# PentaFnord_CtrlBoard_0_91.net
KiCad netlist of a schematic drawn in EAGLE
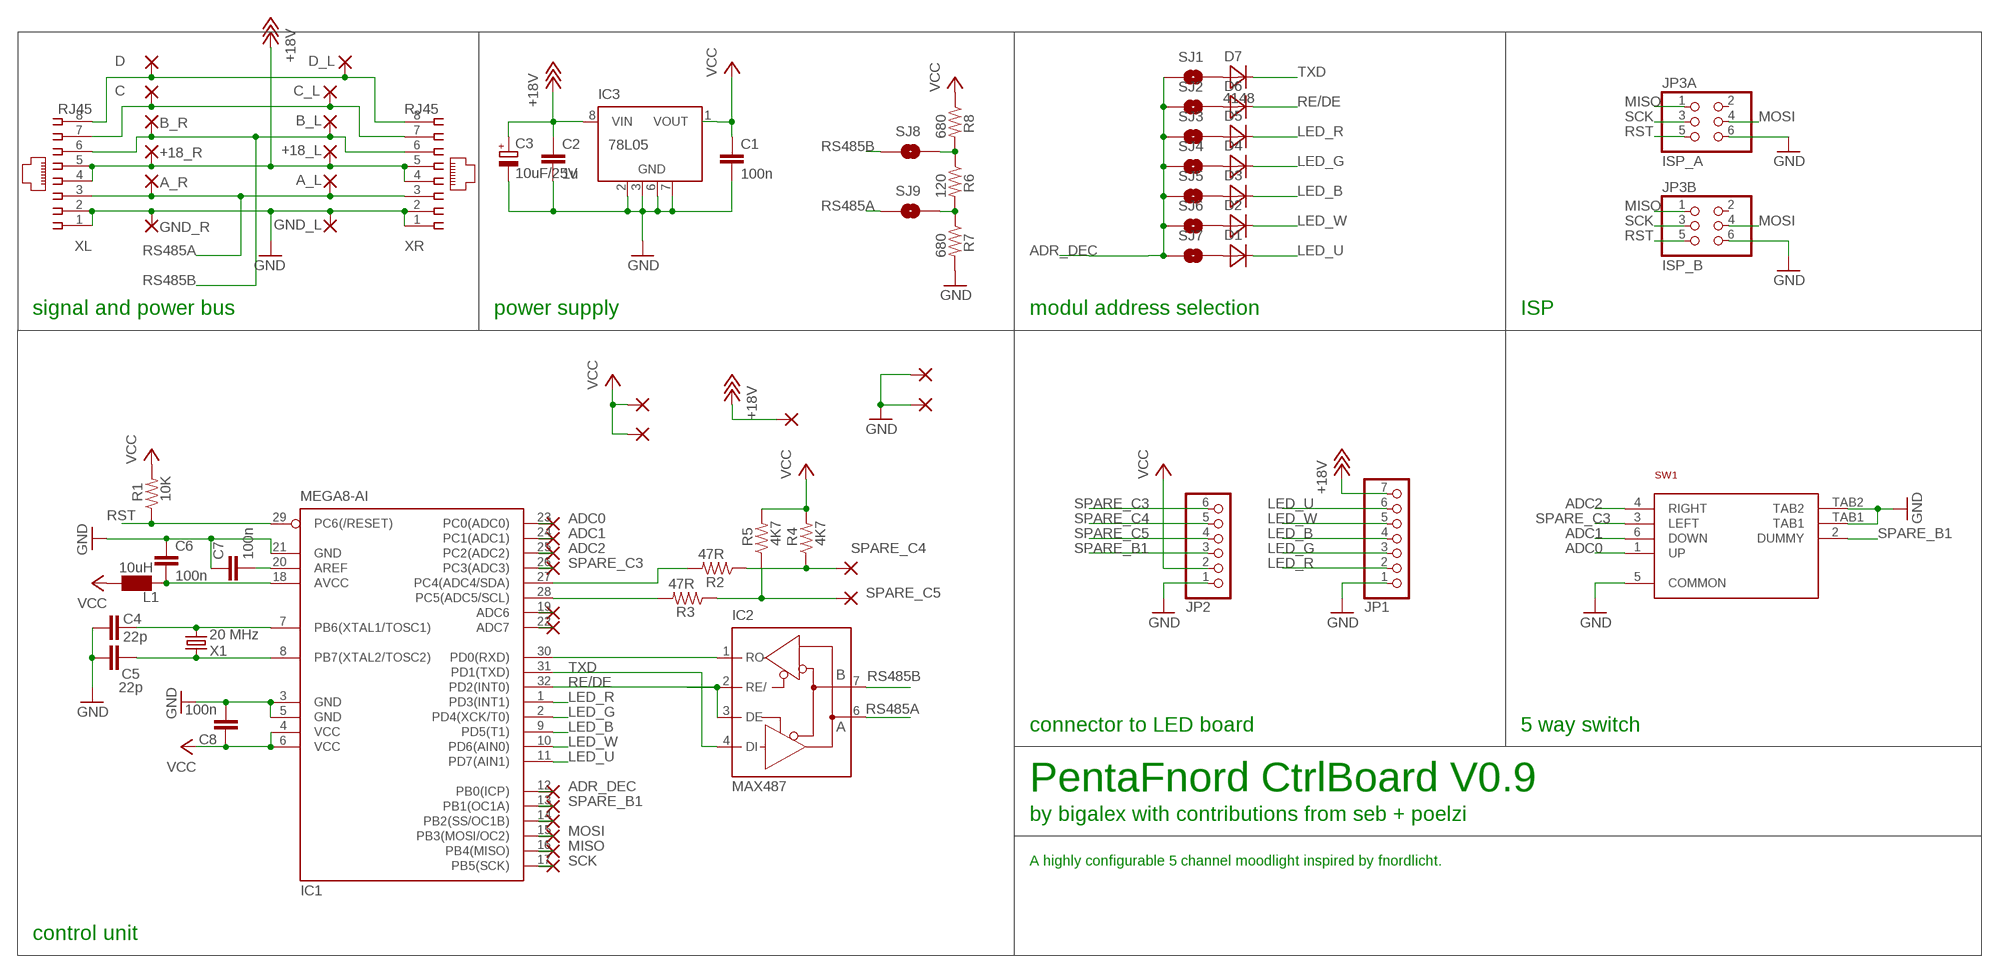
[diagram p0: schematic, sheet 1]

(export (version "E")
  (design (tool "Eeschema 10.0.6"))
  (components
    (comp (ref "+18_L")
      (value "WIREPADSMD2,54-5,08")
      (footprint "eagle-import:SMD2,54-5,08")
      (libsource (lib "eagle-import") (part "WIREPADSMD2,54-5,08"))
    )
    (comp (ref "+18_R")
      (value "WIREPADSMD2,54-5,08")
      (footprint "eagle-import:SMD2,54-5,08")
      (libsource (lib "eagle-import") (part "WIREPADSMD2,54-5,08"))
    )
    (comp (ref "ADC6")
      (value "WIREPADSMD1,27-254")
      (footprint "eagle-import:SMD1,27-2,54")
      (libsource (lib "eagle-import") (part "WIREPADSMD1,27-254"))
    )
    (comp (ref "ADC7")
      (value "WIREPADSMD1,27-254")
      (footprint "eagle-import:SMD1,27-2,54")
      (libsource (lib "eagle-import") (part "WIREPADSMD1,27-254"))
    )
    (comp (ref "A_L")
      (value "WIREPADSMD1,27-254")
      (footprint "eagle-import:SMD1,27-2,54")
      (libsource (lib "eagle-import") (part "WIREPADSMD1,27-254"))
    )
    (comp (ref "A_R")
      (value "WIREPADSMD1,27-254")
      (footprint "eagle-import:SMD1,27-2,54")
      (libsource (lib "eagle-import") (part "WIREPADSMD1,27-254"))
    )
    (comp (ref "B_L")
      (value "WIREPADSMD1,27-254")
      (footprint "eagle-import:SMD1,27-2,54")
      (libsource (lib "eagle-import") (part "WIREPADSMD1,27-254"))
    )
    (comp (ref "B_R")
      (value "WIREPADSMD1,27-254")
      (footprint "eagle-import:SMD1,27-2,54")
      (libsource (lib "eagle-import") (part "WIREPADSMD1,27-254"))
    )
    (comp (ref "C")
      (value "WIREPADSMD1,27-254")
      (footprint "eagle-import:SMD1,27-2,54")
      (libsource (lib "eagle-import") (part "WIREPADSMD1,27-254"))
    )
    (comp (ref "C1")
      (value "100n")
      (footprint "eagle-import:0805")
      (libsource (lib "eagle-import") (part "CAP0805"))
    )
    (comp (ref "C2")
      (value "1u")
      (footprint "eagle-import:0805")
      (libsource (lib "eagle-import") (part "CAP0805"))
    )
    (comp (ref "C3")
      (value "10uF/25V")
      (footprint "eagle-import:SMC_D")
      (libsource (lib "eagle-import") (part "CPOL-EUSMCD"))
    )
    (comp (ref "C4")
      (value "22p")
      (footprint "eagle-import:0805")
      (libsource (lib "eagle-import") (part "CAP0805"))
    )
    (comp (ref "C5")
      (value "22p")
      (footprint "eagle-import:0805")
      (libsource (lib "eagle-import") (part "CAP0805"))
    )
    (comp (ref "C6")
      (value "100n")
      (footprint "eagle-import:0805")
      (libsource (lib "eagle-import") (part "CAP0805"))
    )
    (comp (ref "C7")
      (value "100n")
      (footprint "eagle-import:0805")
      (libsource (lib "eagle-import") (part "CAP0805"))
    )
    (comp (ref "C8")
      (value "100n")
      (footprint "eagle-import:0805")
      (libsource (lib "eagle-import") (part "CAP0805"))
    )
    (comp (ref "C_L")
      (value "WIREPADSMD1,27-254")
      (footprint "eagle-import:SMD1,27-2,54")
      (libsource (lib "eagle-import") (part "WIREPADSMD1,27-254"))
    )
    (comp (ref "D")
      (value "WIREPADSMD1,27-254")
      (footprint "eagle-import:SMD1,27-2,54")
      (libsource (lib "eagle-import") (part "WIREPADSMD1,27-254"))
    )
    (comp (ref "D1")
      (value "DIODE_0805")
      (footprint "eagle-import:DIODE_0805")
      (libsource (lib "eagle-import") (part "DIODE_0805"))
    )
    (comp (ref "D2")
      (value "DIODE_0805")
      (footprint "eagle-import:DIODE_0805")
      (libsource (lib "eagle-import") (part "DIODE_0805"))
    )
    (comp (ref "D3")
      (value "DIODE_0805")
      (footprint "eagle-import:DIODE_0805")
      (libsource (lib "eagle-import") (part "DIODE_0805"))
    )
    (comp (ref "D4")
      (value "DIODE_0805")
      (footprint "eagle-import:DIODE_0805")
      (libsource (lib "eagle-import") (part "DIODE_0805"))
    )
    (comp (ref "D5")
      (value "DIODE_0805")
      (footprint "eagle-import:DIODE_0805")
      (libsource (lib "eagle-import") (part "DIODE_0805"))
    )
    (comp (ref "D6")
      (value "DIODE_0805")
      (footprint "eagle-import:DIODE_0805")
      (libsource (lib "eagle-import") (part "DIODE_0805"))
    )
    (comp (ref "D7")
      (value "4148")
      (footprint "eagle-import:DIODE_0805")
      (libsource (lib "eagle-import") (part "DIODE_0805"))
    )
    (comp (ref "D_L")
      (value "WIREPADSMD1,27-254")
      (footprint "eagle-import:SMD1,27-2,54")
      (libsource (lib "eagle-import") (part "WIREPADSMD1,27-254"))
    )
    (comp (ref "GND_L")
      (value "WIREPADSMD2,54-5,08")
      (footprint "eagle-import:SMD2,54-5,08")
      (libsource (lib "eagle-import") (part "WIREPADSMD2,54-5,08"))
    )
    (comp (ref "GND_R")
      (value "WIREPADSMD2,54-5,08")
      (footprint "eagle-import:SMD2,54-5,08")
      (libsource (lib "eagle-import") (part "WIREPADSMD2,54-5,08"))
    )
    (comp (ref "IC1")
      (value "MEGA8-AI")
      (footprint "eagle-import:TQFP32-08")
      (fields (field (name "MPN") "ATMEGA8-16AU"))
      (libsource (lib "eagle-import") (part "MEGA8-AI"))
    )
    (comp (ref "IC2")
      (value "MAX487")
      (footprint "eagle-import:SO08")
      (fields (field (name "MF") "MAXIM"))
      (libsource (lib "eagle-import") (part "MAX487"))
    )
    (comp (ref "IC3")
      (value "78L05")
      (footprint "eagle-import:SO08")
      (libsource (lib "eagle-import") (part "78LSMD05"))
    )
    (comp (ref "JP1")
      (value "PINHD-1X07_2.54-SMD-REVERSE")
      (footprint "eagle-import:1X07SMD-REVERSE")
      (libsource (lib "eagle-import") (part "PINHD-1X07_2.54-SMD-REVERSE"))
    )
    (comp (ref "JP2")
      (value "PINHD-1X06_2.54-SMD")
      (footprint "eagle-import:1X06SMD")
      (libsource (lib "eagle-import") (part "PINHD-1X06_2.54-SMD"))
    )
    (comp (ref "JP3A")
      (value "ISP_A")
      (footprint "eagle-import:2X03SMD")
      (libsource (lib "eagle-import") (part "PINHD-2X03_2.54-SMD"))
    )
    (comp (ref "JP3B")
      (value "ISP_B")
      (footprint "eagle-import:2X03SMD")
      (libsource (lib "eagle-import") (part "PINHD-2X03_2.54-SMD"))
    )
    (comp (ref "L1")
      (value "10uH")
      (footprint "eagle-import:0805")
      (libsource (lib "eagle-import") (part "BEAD"))
    )
    (comp (ref "PAD1")
      (value "WIREPADSMD1,27-254")
      (footprint "eagle-import:SMD1,27-2,54")
      (libsource (lib "eagle-import") (part "WIREPADSMD1,27-254"))
    )
    (comp (ref "PAD2")
      (value "WIREPADSMD1,27-254")
      (footprint "eagle-import:SMD1,27-2,54")
      (libsource (lib "eagle-import") (part "WIREPADSMD1,27-254"))
    )
    (comp (ref "PAD3")
      (value "WIREPADSMD1,27-254")
      (footprint "eagle-import:SMD1,27-2,54")
      (libsource (lib "eagle-import") (part "WIREPADSMD1,27-254"))
    )
    (comp (ref "PAD4")
      (value "WIREPADSMD1,27-254")
      (footprint "eagle-import:SMD1,27-2,54")
      (libsource (lib "eagle-import") (part "WIREPADSMD1,27-254"))
    )
    (comp (ref "PAD5")
      (value "WIREPADSMD1,27-254")
      (footprint "eagle-import:SMD1,27-2,54")
      (libsource (lib "eagle-import") (part "WIREPADSMD1,27-254"))
    )
    (comp (ref "PB0")
      (value "WIREPADSMD1,27-254")
      (footprint "eagle-import:SMD1,27-2,54")
      (libsource (lib "eagle-import") (part "WIREPADSMD1,27-254"))
    )
    (comp (ref "PB1")
      (value "WIREPADSMD1,27-254")
      (footprint "eagle-import:SMD1,27-2,54")
      (libsource (lib "eagle-import") (part "WIREPADSMD1,27-254"))
    )
    (comp (ref "PB2")
      (value "WIREPADSMD1,27-254")
      (footprint "eagle-import:SMD1,27-2,54")
      (libsource (lib "eagle-import") (part "WIREPADSMD1,27-254"))
    )
    (comp (ref "PB3")
      (value "WIREPADSMD1,27-254")
      (footprint "eagle-import:SMD1,27-2,54")
      (libsource (lib "eagle-import") (part "WIREPADSMD1,27-254"))
    )
    (comp (ref "PB4")
      (value "WIREPADSMD1,27-254")
      (footprint "eagle-import:SMD1,27-2,54")
      (libsource (lib "eagle-import") (part "WIREPADSMD1,27-254"))
    )
    (comp (ref "PB5")
      (value "WIREPADSMD1,27-254")
      (footprint "eagle-import:SMD1,27-2,54")
      (libsource (lib "eagle-import") (part "WIREPADSMD1,27-254"))
    )
    (comp (ref "PC0")
      (value "WIREPADSMD1,27-254")
      (footprint "eagle-import:SMD1,27-2,54")
      (libsource (lib "eagle-import") (part "WIREPADSMD1,27-254"))
    )
    (comp (ref "PC1")
      (value "WIREPADSMD1,27-254")
      (footprint "eagle-import:SMD1,27-2,54")
      (libsource (lib "eagle-import") (part "WIREPADSMD1,27-254"))
    )
    (comp (ref "PC2")
      (value "WIREPADSMD1,27-254")
      (footprint "eagle-import:SMD1,27-2,54")
      (libsource (lib "eagle-import") (part "WIREPADSMD1,27-254"))
    )
    (comp (ref "PC3")
      (value "WIREPADSMD1,27-254")
      (footprint "eagle-import:SMD1,27-2,54")
      (libsource (lib "eagle-import") (part "WIREPADSMD1,27-254"))
    )
    (comp (ref "PC4")
      (value "WIREPADSMD1,27-254")
      (footprint "eagle-import:SMD1,27-2,54")
      (libsource (lib "eagle-import") (part "WIREPADSMD1,27-254"))
    )
    (comp (ref "PC5")
      (value "WIREPADSMD1,27-254")
      (footprint "eagle-import:SMD1,27-2,54")
      (libsource (lib "eagle-import") (part "WIREPADSMD1,27-254"))
    )
    (comp (ref "R1")
      (value "10K")
      (footprint "eagle-import:0805")
      (libsource (lib "eagle-import") (part "RESISTOR0805-RES"))
    )
    (comp (ref "R2")
      (value "47R")
      (footprint "eagle-import:0805")
      (libsource (lib "eagle-import") (part "RESISTOR0805-RES"))
    )
    (comp (ref "R3")
      (value "47R")
      (footprint "eagle-import:0805")
      (libsource (lib "eagle-import") (part "RESISTOR0805-RES"))
    )
    (comp (ref "R4")
      (value "4K7")
      (footprint "eagle-import:0805")
      (libsource (lib "eagle-import") (part "RESISTOR0805-RES"))
    )
    (comp (ref "R5")
      (value "4K7")
      (footprint "eagle-import:0805")
      (libsource (lib "eagle-import") (part "RESISTOR0805-RES"))
    )
    (comp (ref "R6")
      (value "120")
      (footprint "eagle-import:0805")
      (libsource (lib "eagle-import") (part "RESISTOR0805-RES"))
    )
    (comp (ref "R7")
      (value "680")
      (footprint "eagle-import:0805")
      (libsource (lib "eagle-import") (part "RESISTOR0805-RES"))
    )
    (comp (ref "R8")
      (value "680")
      (footprint "eagle-import:0805")
      (libsource (lib "eagle-import") (part "RESISTOR0805-RES"))
    )
    (comp (ref "SJ1")
      (value "SOLDERJUMPERNO")
      (footprint "eagle-import:SJ_2S-NO")
      (libsource (lib "eagle-import") (part "SOLDERJUMPERNO"))
    )
    (comp (ref "SJ2")
      (value "SOLDERJUMPERNO")
      (footprint "eagle-import:SJ_2S-NO")
      (libsource (lib "eagle-import") (part "SOLDERJUMPERNO"))
    )
    (comp (ref "SJ3")
      (value "SOLDERJUMPERNO")
      (footprint "eagle-import:SJ_2S-NO")
      (libsource (lib "eagle-import") (part "SOLDERJUMPERNO"))
    )
    (comp (ref "SJ4")
      (value "SOLDERJUMPERNO")
      (footprint "eagle-import:SJ_2S-NO")
      (libsource (lib "eagle-import") (part "SOLDERJUMPERNO"))
    )
    (comp (ref "SJ5")
      (value "SOLDERJUMPERNO")
      (footprint "eagle-import:SJ_2S-NO")
      (libsource (lib "eagle-import") (part "SOLDERJUMPERNO"))
    )
    (comp (ref "SJ6")
      (value "SOLDERJUMPERNO")
      (footprint "eagle-import:SJ_2S-NO")
      (libsource (lib "eagle-import") (part "SOLDERJUMPERNO"))
    )
    (comp (ref "SJ7")
      (value "SOLDERJUMPERNO")
      (footprint "eagle-import:SJ_2S-NO")
      (libsource (lib "eagle-import") (part "SOLDERJUMPERNO"))
    )
    (comp (ref "SJ8")
      (value "SOLDERJUMPERNO")
      (footprint "eagle-import:SJ_2S-NO")
      (libsource (lib "eagle-import") (part "SOLDERJUMPERNO"))
    )
    (comp (ref "SJ9")
      (value "SOLDERJUMPERNO")
      (footprint "eagle-import:SJ_2S-NO")
      (libsource (lib "eagle-import") (part "SOLDERJUMPERNO"))
    )
    (comp (ref "SW1")
      (value "MCMT5-F-VADAPTED_FOOTPRINT")
      (footprint "eagle-import:MCMT5-F-V_ADAPTED")
      (libsource (lib "eagle-import") (part "MCMT5-F-VADAPTED_FOOTPRINT"))
    )
    (comp (ref "X1")
      (value "20 MHz")
      (footprint "eagle-import:HC49UP-SMALL")
      (libsource (lib "eagle-import") (part "CRYSTALSMD-SMALLER"))
    )
    (comp (ref "XL")
      (value "RJ45")
      (footprint "eagle-import:85502-5008-SMALL")
      (libsource (lib "eagle-import") (part "RJ45-SMDRJ45-SMALL"))
    )
    (comp (ref "XR")
      (value "RJ45")
      (footprint "eagle-import:85502-5008-SMALL")
      (libsource (lib "eagle-import") (part "RJ45-SMDRJ45-SMALL"))
    )
  )
  (nets
    (net (code "1") (name "+18V") (class "Default")
      (node (ref "+18_L") (pin "1") (pinfunction "P_1") (pintype "passive"))
      (node (ref "+18_R") (pin "1") (pinfunction "P_1") (pintype "passive"))
      (node (ref "C2") (pin "1") (pinfunction "1_1") (pintype "passive"))
      (node (ref "C3") (pin "+") (pinfunction "+_+") (pintype "passive"))
      (node (ref "IC3") (pin "8") (pinfunction "VIN_8") (pintype "passive"))
      (node (ref "JP1") (pin "7") (pinfunction "7_7") (pintype "passive"))
      (node (ref "PAD2") (pin "1") (pinfunction "P_1") (pintype "passive"))
      (node (ref "XL") (pin "4") (pinfunction "4_4") (pintype "passive"))
      (node (ref "XL") (pin "5") (pinfunction "5_5") (pintype "passive"))
      (node (ref "XR") (pin "4") (pinfunction "4_4") (pintype "passive"))
      (node (ref "XR") (pin "5") (pinfunction "5_5") (pintype "passive"))
    )
    (net (code "2") (name "/ADC0") (class "Default")
      (node (ref "IC1") (pin "23") (pinfunction "PC0(ADC0)_23") (pintype "bidirectional"))
      (node (ref "PC0") (pin "1") (pinfunction "P_1") (pintype "passive"))
      (node (ref "SW1") (pin "1") (pinfunction "UP_1") (pintype "bidirectional"))
    )
    (net (code "3") (name "/ADC1") (class "Default")
      (node (ref "IC1") (pin "24") (pinfunction "PC1(ADC1)_24") (pintype "bidirectional"))
      (node (ref "PC1") (pin "1") (pinfunction "P_1") (pintype "passive"))
      (node (ref "SW1") (pin "6") (pinfunction "DOWN_6") (pintype "bidirectional"))
    )
    (net (code "4") (name "/ADC2") (class "Default")
      (node (ref "IC1") (pin "25") (pinfunction "PC2(ADC2)_25") (pintype "bidirectional"))
      (node (ref "PC2") (pin "1") (pinfunction "P_1") (pintype "passive"))
      (node (ref "SW1") (pin "4") (pinfunction "RIGHT_4") (pintype "bidirectional"))
    )
    (net (code "5") (name "/ADR_DEC") (class "Default")
      (node (ref "IC1") (pin "12") (pinfunction "PB0(ICP)_12") (pintype "bidirectional"))
      (node (ref "PB0") (pin "1") (pinfunction "P_1") (pintype "passive"))
      (node (ref "SJ1") (pin "1") (pinfunction "1_1") (pintype "passive"))
      (node (ref "SJ2") (pin "1") (pinfunction "1_1") (pintype "passive"))
      (node (ref "SJ3") (pin "1") (pinfunction "1_1") (pintype "passive"))
      (node (ref "SJ4") (pin "1") (pinfunction "1_1") (pintype "passive"))
      (node (ref "SJ5") (pin "1") (pinfunction "1_1") (pintype "passive"))
      (node (ref "SJ6") (pin "1") (pinfunction "1_1") (pintype "passive"))
      (node (ref "SJ7") (pin "1") (pinfunction "1_1") (pintype "passive"))
    )
    (net (code "6") (name "/LED_B") (class "Default")
      (node (ref "D3") (pin "1") (pinfunction "C_1") (pintype "passive"))
      (node (ref "IC1") (pin "9") (pinfunction "PD5(T1)_9") (pintype "bidirectional"))
      (node (ref "JP1") (pin "4") (pinfunction "4_4") (pintype "passive"))
    )
    (net (code "7") (name "/LED_G") (class "Default")
      (node (ref "D4") (pin "1") (pinfunction "C_1") (pintype "passive"))
      (node (ref "IC1") (pin "2") (pinfunction "PD4(XCK/T0)_2") (pintype "bidirectional"))
      (node (ref "JP1") (pin "3") (pinfunction "3_3") (pintype "passive"))
    )
    (net (code "8") (name "/LED_R") (class "Default")
      (node (ref "D5") (pin "1") (pinfunction "C_1") (pintype "passive"))
      (node (ref "IC1") (pin "1") (pinfunction "PD3(INT1)_1") (pintype "bidirectional"))
      (node (ref "JP1") (pin "2") (pinfunction "2_2") (pintype "passive"))
    )
    (net (code "9") (name "/LED_U") (class "Default")
      (node (ref "D1") (pin "1") (pinfunction "C_1") (pintype "passive"))
      (node (ref "IC1") (pin "11") (pinfunction "PD7(AIN1)_11") (pintype "bidirectional"))
      (node (ref "JP1") (pin "6") (pinfunction "6_6") (pintype "passive"))
    )
    (net (code "10") (name "/LED_W") (class "Default")
      (node (ref "D2") (pin "1") (pinfunction "C_1") (pintype "passive"))
      (node (ref "IC1") (pin "10") (pinfunction "PD6(AIN0)_10") (pintype "bidirectional"))
      (node (ref "JP1") (pin "5") (pinfunction "5_5") (pintype "passive"))
    )
    (net (code "11") (name "/MISO") (class "Default")
      (node (ref "IC1") (pin "16") (pinfunction "PB4(MISO)_16") (pintype "bidirectional"))
      (node (ref "JP3A") (pin "1") (pinfunction "1_1") (pintype "passive"))
      (node (ref "JP3B") (pin "1") (pinfunction "1_1") (pintype "passive"))
      (node (ref "PB4") (pin "1") (pinfunction "P_1") (pintype "passive"))
    )
    (net (code "12") (name "/MOSI") (class "Default")
      (node (ref "IC1") (pin "15") (pinfunction "PB3(MOSI/OC2)_15") (pintype "bidirectional"))
      (node (ref "JP3A") (pin "4") (pinfunction "4_4") (pintype "passive"))
      (node (ref "JP3B") (pin "4") (pinfunction "4_4") (pintype "passive"))
      (node (ref "PB3") (pin "1") (pinfunction "P_1") (pintype "passive"))
    )
    (net (code "13") (name "/RE{slash}DE") (class "Default")
      (node (ref "D6") (pin "1") (pinfunction "C_1") (pintype "passive"))
      (node (ref "IC1") (pin "32") (pinfunction "PD2(INT0)_32") (pintype "bidirectional"))
      (node (ref "IC2") (pin "2") (pinfunction "RE/_2") (pintype "input"))
      (node (ref "IC2") (pin "3") (pinfunction "DE_3") (pintype "input"))
    )
    (net (code "14") (name "/RS485A") (class "Default")
      (node (ref "A_L") (pin "1") (pinfunction "P_1") (pintype "passive"))
      (node (ref "A_R") (pin "1") (pinfunction "P_1") (pintype "passive"))
      (node (ref "IC2") (pin "6") (pinfunction "A_6") (pintype "passive"))
      (node (ref "SJ9") (pin "1") (pinfunction "1_1") (pintype "passive"))
      (node (ref "XL") (pin "3") (pinfunction "3_3") (pintype "passive"))
      (node (ref "XR") (pin "3") (pinfunction "3_3") (pintype "passive"))
    )
    (net (code "15") (name "/RS485B") (class "Default")
      (node (ref "B_L") (pin "1") (pinfunction "P_1") (pintype "passive"))
      (node (ref "B_R") (pin "1") (pinfunction "P_1") (pintype "passive"))
      (node (ref "IC2") (pin "7") (pinfunction "B_7") (pintype "passive"))
      (node (ref "SJ8") (pin "1") (pinfunction "1_1") (pintype "passive"))
      (node (ref "XL") (pin "6") (pinfunction "6_6") (pintype "passive"))
      (node (ref "XR") (pin "6") (pinfunction "6_6") (pintype "passive"))
    )
    (net (code "16") (name "/RST") (class "Default")
      (node (ref "IC1") (pin "29") (pinfunction "PC6(/RESET)_29") (pintype "bidirectional"))
      (node (ref "JP3A") (pin "5") (pinfunction "5_5") (pintype "passive"))
      (node (ref "JP3B") (pin "5") (pinfunction "5_5") (pintype "passive"))
      (node (ref "R1") (pin "1") (pinfunction "1_1") (pintype "passive"))
    )
    (net (code "17") (name "/SCK") (class "Default")
      (node (ref "IC1") (pin "17") (pinfunction "PB5(SCK)_17") (pintype "bidirectional"))
      (node (ref "JP3A") (pin "3") (pinfunction "3_3") (pintype "passive"))
      (node (ref "JP3B") (pin "3") (pinfunction "3_3") (pintype "passive"))
      (node (ref "PB5") (pin "1") (pinfunction "P_1") (pintype "passive"))
    )
    (net (code "18") (name "/SPARE_B1") (class "Default")
      (node (ref "IC1") (pin "13") (pinfunction "PB1(OC1A)_13") (pintype "bidirectional"))
      (node (ref "JP2") (pin "3") (pinfunction "3_3") (pintype "passive"))
      (node (ref "PB1") (pin "1") (pinfunction "P_1") (pintype "passive"))
      (node (ref "SW1") (pin "2") (pinfunction "DUMMY_2") (pintype "bidirectional"))
    )
    (net (code "19") (name "/SPARE_C3") (class "Default")
      (node (ref "IC1") (pin "26") (pinfunction "PC3(ADC3)_26") (pintype "bidirectional"))
      (node (ref "JP2") (pin "6") (pinfunction "6_6") (pintype "passive"))
      (node (ref "PC3") (pin "1") (pinfunction "P_1") (pintype "passive"))
      (node (ref "SW1") (pin "3") (pinfunction "LEFT_3") (pintype "bidirectional"))
    )
    (net (code "20") (name "/SPARE_C4") (class "Default")
      (node (ref "JP2") (pin "5") (pinfunction "5_5") (pintype "passive"))
      (node (ref "PC4") (pin "1") (pinfunction "P_1") (pintype "passive"))
      (node (ref "R2") (pin "1") (pinfunction "1_1") (pintype "passive"))
      (node (ref "R4") (pin "1") (pinfunction "1_1") (pintype "passive"))
    )
    (net (code "21") (name "/SPARE_C5") (class "Default")
      (node (ref "JP2") (pin "4") (pinfunction "4_4") (pintype "passive"))
      (node (ref "PC5") (pin "1") (pinfunction "P_1") (pintype "passive"))
      (node (ref "R3") (pin "1") (pinfunction "1_1") (pintype "passive"))
      (node (ref "R5") (pin "1") (pinfunction "1_1") (pintype "passive"))
    )
    (net (code "22") (name "/TXD") (class "Default")
      (node (ref "D7") (pin "1") (pinfunction "C_1") (pintype "passive"))
      (node (ref "IC1") (pin "31") (pinfunction "PD1(TXD)_31") (pintype "bidirectional"))
      (node (ref "IC2") (pin "4") (pinfunction "DI_4") (pintype "input"))
    )
    (net (code "23") (name "GND") (class "Default")
      (node (ref "C1") (pin "2") (pinfunction "2_2") (pintype "passive"))
      (node (ref "C2") (pin "2") (pinfunction "2_2") (pintype "passive"))
      (node (ref "C3") (pin "-") (pinfunction "-_-") (pintype "passive"))
      (node (ref "C4") (pin "1") (pinfunction "1_1") (pintype "passive"))
      (node (ref "C5") (pin "1") (pinfunction "1_1") (pintype "passive"))
      (node (ref "C6") (pin "1") (pinfunction "1_1") (pintype "passive"))
      (node (ref "C7") (pin "1") (pinfunction "1_1") (pintype "passive"))
      (node (ref "C8") (pin "2") (pinfunction "2_2") (pintype "passive"))
      (node (ref "GND_L") (pin "1") (pinfunction "P_1") (pintype "passive"))
      (node (ref "GND_R") (pin "1") (pinfunction "P_1") (pintype "passive"))
      (node (ref "IC1") (pin "21") (pinfunction "GND_21") (pintype "power_in"))
      (node (ref "IC1") (pin "3") (pinfunction "GND_3") (pintype "power_in"))
      (node (ref "IC1") (pin "5") (pinfunction "GND_5") (pintype "power_in"))
      (node (ref "IC3") (pin "2") (pinfunction "GND_2") (pintype "power_in"))
      (node (ref "IC3") (pin "3") (pinfunction "GND_3") (pintype "power_in"))
      (node (ref "IC3") (pin "6") (pinfunction "GND_6") (pintype "power_in"))
      (node (ref "IC3") (pin "7") (pinfunction "GND_7") (pintype "power_in"))
      (node (ref "JP1") (pin "1") (pinfunction "1_1") (pintype "passive"))
      (node (ref "JP2") (pin "1") (pinfunction "1_1") (pintype "passive"))
      (node (ref "JP3A") (pin "6") (pinfunction "6_6") (pintype "passive"))
      (node (ref "JP3B") (pin "6") (pinfunction "6_6") (pintype "passive"))
      (node (ref "PAD1") (pin "1") (pinfunction "P_1") (pintype "passive"))
      (node (ref "PAD5") (pin "1") (pinfunction "P_1") (pintype "passive"))
      (node (ref "R7") (pin "2") (pinfunction "2_2") (pintype "passive"))
      (node (ref "SW1") (pin "5") (pinfunction "COMMON_5") (pintype "bidirectional"))
      (node (ref "SW1") (pin "TAB1") (pinfunction "TAB1_TAB1") (pintype "bidirectional"))
      (node (ref "SW1") (pin "TAB2") (pinfunction "TAB2_TAB2") (pintype "bidirectional"))
      (node (ref "XL") (pin "1") (pinfunction "1_1") (pintype "passive"))
      (node (ref "XL") (pin "2") (pinfunction "2_2") (pintype "passive"))
      (node (ref "XR") (pin "1") (pinfunction "1_1") (pintype "passive"))
      (node (ref "XR") (pin "2") (pinfunction "2_2") (pintype "passive"))
    )
    (net (code "24") (name "Net-(ADC6-P)") (class "Default")
      (node (ref "ADC6") (pin "1") (pinfunction "P_1") (pintype "passive"))
      (node (ref "IC1") (pin "19") (pinfunction "ADC6_19") (pintype "bidirectional"))
    )
    (net (code "25") (name "Net-(ADC7-P)") (class "Default")
      (node (ref "ADC7") (pin "1") (pinfunction "P_1") (pintype "passive"))
      (node (ref "IC1") (pin "22") (pinfunction "ADC7_22") (pintype "bidirectional"))
    )
    (net (code "26") (name "Net-(C-P)") (class "Default")
      (node (ref "C") (pin "1") (pinfunction "P_1") (pintype "passive"))
      (node (ref "C_L") (pin "1") (pinfunction "P_1") (pintype "passive"))
      (node (ref "XL") (pin "7") (pinfunction "7_7") (pintype "passive"))
      (node (ref "XR") (pin "7") (pinfunction "7_7") (pintype "passive"))
    )
    (net (code "27") (name "Net-(D-P)") (class "Default")
      (node (ref "D") (pin "1") (pinfunction "P_1") (pintype "passive"))
      (node (ref "D_L") (pin "1") (pinfunction "P_1") (pintype "passive"))
      (node (ref "XL") (pin "8") (pinfunction "8_8") (pintype "passive"))
      (node (ref "XR") (pin "8") (pinfunction "8_8") (pintype "passive"))
    )
    (net (code "28") (name "Net-(D1-A)") (class "Default")
      (node (ref "D1") (pin "2") (pinfunction "A_2") (pintype "passive"))
      (node (ref "SJ7") (pin "2") (pinfunction "2_2") (pintype "passive"))
    )
    (net (code "29") (name "Net-(D2-A)") (class "Default")
      (node (ref "D2") (pin "2") (pinfunction "A_2") (pintype "passive"))
      (node (ref "SJ6") (pin "2") (pinfunction "2_2") (pintype "passive"))
    )
    (net (code "30") (name "Net-(D3-A)") (class "Default")
      (node (ref "D3") (pin "2") (pinfunction "A_2") (pintype "passive"))
      (node (ref "SJ5") (pin "2") (pinfunction "2_2") (pintype "passive"))
    )
    (net (code "31") (name "Net-(D4-A)") (class "Default")
      (node (ref "D4") (pin "2") (pinfunction "A_2") (pintype "passive"))
      (node (ref "SJ4") (pin "2") (pinfunction "2_2") (pintype "passive"))
    )
    (net (code "32") (name "Net-(D5-A)") (class "Default")
      (node (ref "D5") (pin "2") (pinfunction "A_2") (pintype "passive"))
      (node (ref "SJ3") (pin "2") (pinfunction "2_2") (pintype "passive"))
    )
    (net (code "33") (name "Net-(D6-A)") (class "Default")
      (node (ref "D6") (pin "2") (pinfunction "A_2") (pintype "passive"))
      (node (ref "SJ2") (pin "2") (pinfunction "2_2") (pintype "passive"))
    )
    (net (code "34") (name "Net-(D7-A)") (class "Default")
      (node (ref "D7") (pin "2") (pinfunction "A_2") (pintype "passive"))
      (node (ref "SJ1") (pin "2") (pinfunction "2_2") (pintype "passive"))
    )
    (net (code "35") (name "Net-(IC1-AREF)") (class "Default")
      (node (ref "C7") (pin "2") (pinfunction "2_2") (pintype "passive"))
      (node (ref "IC1") (pin "20") (pinfunction "AREF_20") (pintype "passive"))
    )
    (net (code "36") (name "Net-(IC1-AVCC)") (class "Default")
      (node (ref "C6") (pin "2") (pinfunction "2_2") (pintype "passive"))
      (node (ref "IC1") (pin "18") (pinfunction "AVCC_18") (pintype "power_in"))
      (node (ref "L1") (pin "2") (pinfunction "2_2") (pintype "passive"))
    )
    (net (code "37") (name "Net-(IC1-PB2(SS{slash}OC1B))") (class "Default")
      (node (ref "IC1") (pin "14") (pinfunction "PB2(SS/OC1B)_14") (pintype "bidirectional"))
      (node (ref "PB2") (pin "1") (pinfunction "P_1") (pintype "passive"))
    )
    (net (code "38") (name "Net-(IC1-PB6(XTAL1{slash}TOSC1))") (class "Default")
      (node (ref "C4") (pin "2") (pinfunction "2_2") (pintype "passive"))
      (node (ref "IC1") (pin "7") (pinfunction "PB6(XTAL1/TOSC1)_7") (pintype "bidirectional"))
      (node (ref "X1") (pin "1") (pinfunction "1_1") (pintype "passive"))
    )
    (net (code "39") (name "Net-(IC1-PB7(XTAL2{slash}TOSC2))") (class "Default")
      (node (ref "C5") (pin "2") (pinfunction "2_2") (pintype "passive"))
      (node (ref "IC1") (pin "8") (pinfunction "PB7(XTAL2/TOSC2)_8") (pintype "bidirectional"))
      (node (ref "X1") (pin "2") (pinfunction "2_2") (pintype "passive"))
    )
    (net (code "40") (name "Net-(IC1-PC4(ADC4{slash}SDA))") (class "Default")
      (node (ref "IC1") (pin "27") (pinfunction "PC4(ADC4/SDA)_27") (pintype "bidirectional"))
      (node (ref "R2") (pin "2") (pinfunction "2_2") (pintype "passive"))
    )
    (net (code "41") (name "Net-(IC1-PC5(ADC5{slash}SCL))") (class "Default")
      (node (ref "IC1") (pin "28") (pinfunction "PC5(ADC5/SCL)_28") (pintype "bidirectional"))
      (node (ref "R3") (pin "2") (pinfunction "2_2") (pintype "passive"))
    )
    (net (code "42") (name "Net-(IC1-PD0(RXD))") (class "Default")
      (node (ref "IC1") (pin "30") (pinfunction "PD0(RXD)_30") (pintype "bidirectional"))
      (node (ref "IC2") (pin "1") (pinfunction "RO_1") (pintype "output"))
    )
    (net (code "43") (name "Net-(R6-Pad1)") (class "Default")
      (node (ref "R6") (pin "1") (pinfunction "1_1") (pintype "passive"))
      (node (ref "R8") (pin "2") (pinfunction "2_2") (pintype "passive"))
      (node (ref "SJ8") (pin "2") (pinfunction "2_2") (pintype "passive"))
    )
    (net (code "44") (name "Net-(R6-Pad2)") (class "Default")
      (node (ref "R6") (pin "2") (pinfunction "2_2") (pintype "passive"))
      (node (ref "R7") (pin "1") (pinfunction "1_1") (pintype "passive"))
      (node (ref "SJ9") (pin "2") (pinfunction "2_2") (pintype "passive"))
    )
    (net (code "45") (name "VCC") (class "Default")
      (node (ref "C1") (pin "1") (pinfunction "1_1") (pintype "passive"))
      (node (ref "C8") (pin "1") (pinfunction "1_1") (pintype "passive"))
      (node (ref "IC1") (pin "4") (pinfunction "VCC_4") (pintype "power_in"))
      (node (ref "IC1") (pin "6") (pinfunction "VCC_6") (pintype "power_in"))
      (node (ref "IC3") (pin "1") (pinfunction "VOUT_1") (pintype "output"))
      (node (ref "JP2") (pin "2") (pinfunction "2_2") (pintype "passive"))
      (node (ref "L1") (pin "1") (pinfunction "1_1") (pintype "passive"))
      (node (ref "PAD3") (pin "1") (pinfunction "P_1") (pintype "passive"))
      (node (ref "PAD4") (pin "1") (pinfunction "P_1") (pintype "passive"))
      (node (ref "R1") (pin "2") (pinfunction "2_2") (pintype "passive"))
      (node (ref "R4") (pin "2") (pinfunction "2_2") (pintype "passive"))
      (node (ref "R5") (pin "2") (pinfunction "2_2") (pintype "passive"))
      (node (ref "R8") (pin "1") (pinfunction "1_1") (pintype "passive"))
    )
    (net (code "46") (name "unconnected-(JP3A-Pad2)") (class "Default")
      (node (ref "JP3A") (pin "2") (pinfunction "2_2") (pintype "passive"))
    )
    (net (code "47") (name "unconnected-(JP3B-Pad2)") (class "Default")
      (node (ref "JP3B") (pin "2") (pinfunction "2_2") (pintype "passive"))
    )
  )
)
